# smd_test_rig_with_pico.net
KiCad netlist of a schematic drawn in EAGLE
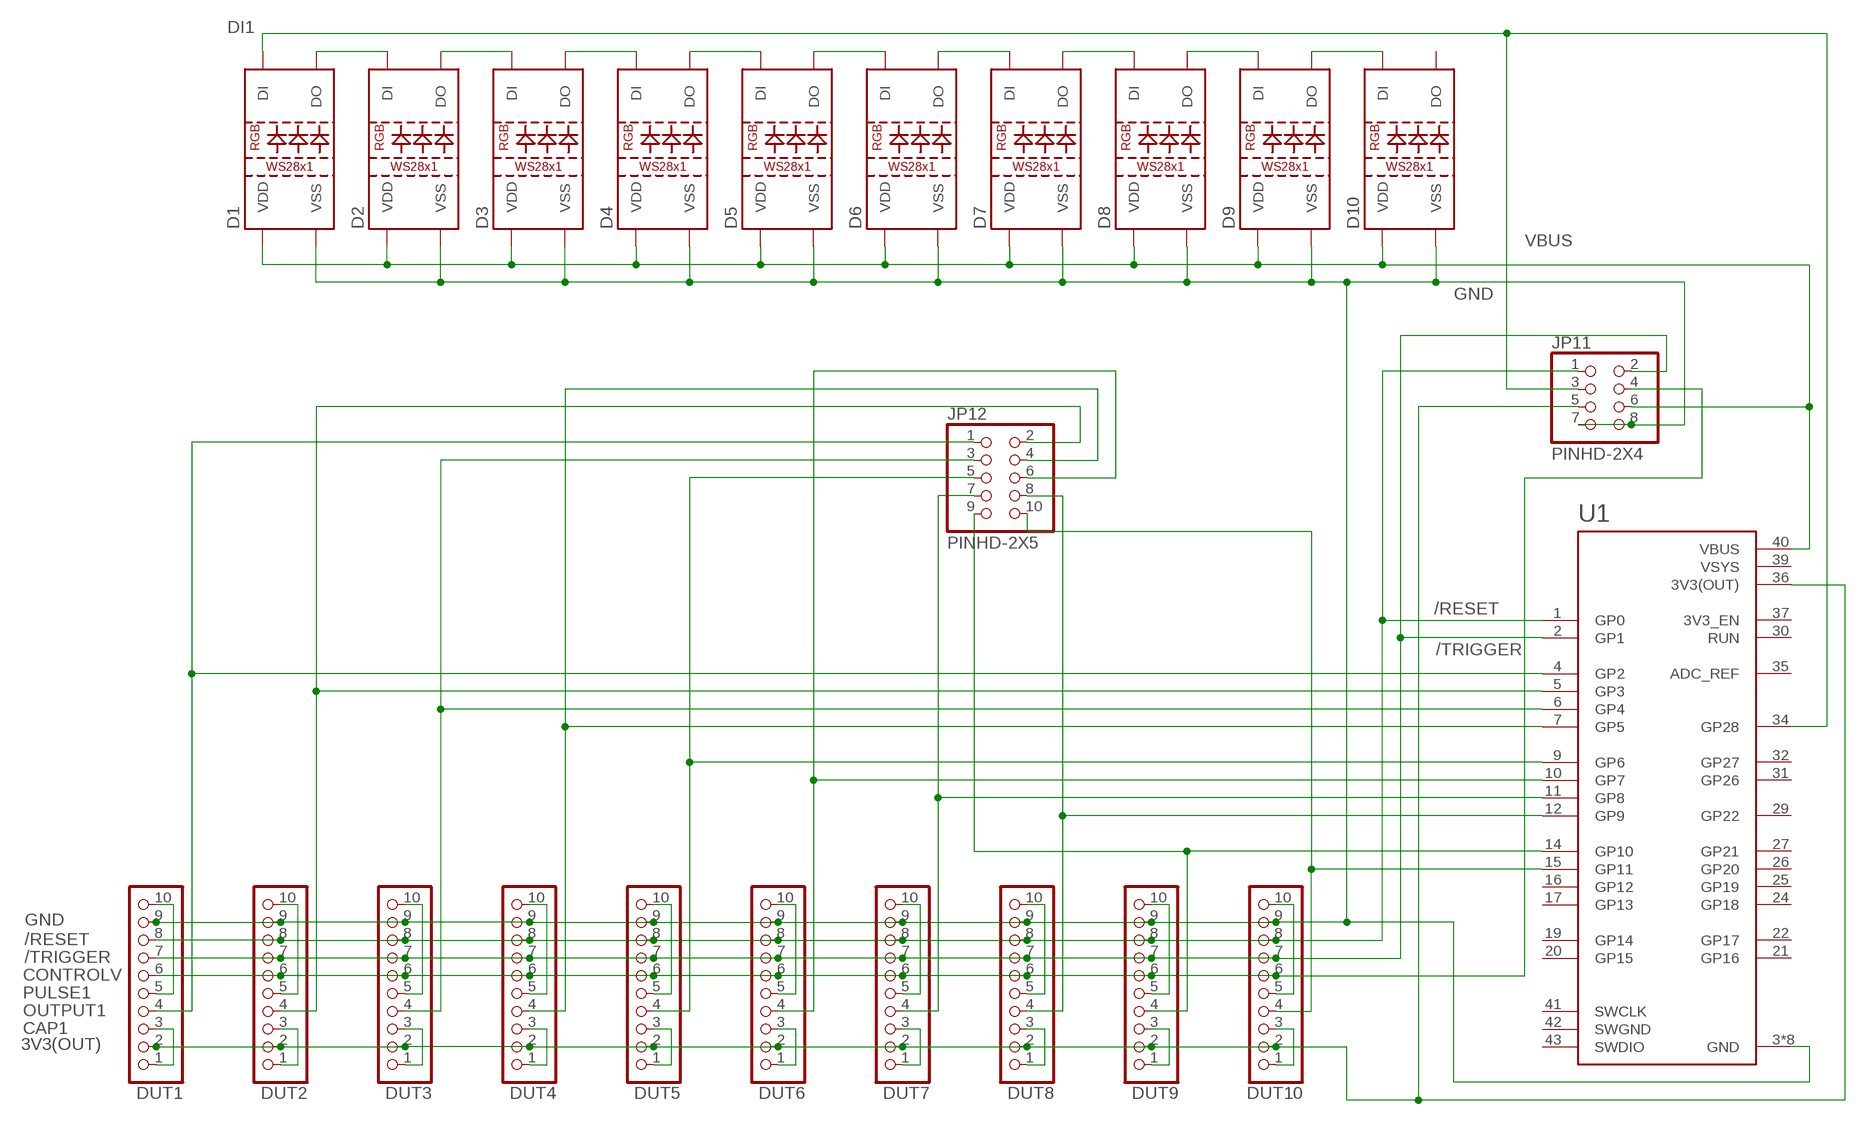
[diagram p0: schematic, sheet 1]

(export (version "E")
  (design (tool "Eeschema 10.0.6"))
  (components
    (comp (ref "D1")
      (value "WS2812B")
      (footprint "eagle-import:WS2812B")
      (libsource (lib "eagle-import") (part "WS2812B"))
    )
    (comp (ref "D2")
      (value "WS2812B")
      (footprint "eagle-import:WS2812B")
      (libsource (lib "eagle-import") (part "WS2812B"))
    )
    (comp (ref "D3")
      (value "WS2812B")
      (footprint "eagle-import:WS2812B")
      (libsource (lib "eagle-import") (part "WS2812B"))
    )
    (comp (ref "D4")
      (value "WS2812B")
      (footprint "eagle-import:WS2812B")
      (libsource (lib "eagle-import") (part "WS2812B"))
    )
    (comp (ref "D5")
      (value "WS2812B")
      (footprint "eagle-import:WS2812B")
      (libsource (lib "eagle-import") (part "WS2812B"))
    )
    (comp (ref "D6")
      (value "WS2812B")
      (footprint "eagle-import:WS2812B")
      (libsource (lib "eagle-import") (part "WS2812B"))
    )
    (comp (ref "D7")
      (value "WS2812B")
      (footprint "eagle-import:WS2812B")
      (libsource (lib "eagle-import") (part "WS2812B"))
    )
    (comp (ref "D8")
      (value "WS2812B")
      (footprint "eagle-import:WS2812B")
      (libsource (lib "eagle-import") (part "WS2812B"))
    )
    (comp (ref "D9")
      (value "WS2812B")
      (footprint "eagle-import:WS2812B")
      (libsource (lib "eagle-import") (part "WS2812B"))
    )
    (comp (ref "D10")
      (value "WS2812B")
      (footprint "eagle-import:WS2812B")
      (libsource (lib "eagle-import") (part "WS2812B"))
    )
    (comp (ref "DUT1")
      (value "PINHD-1X10")
      (footprint "eagle-import:1X10")
      (libsource (lib "eagle-import") (part "PINHD-1X10"))
    )
    (comp (ref "DUT2")
      (value "PINHD-1X10")
      (footprint "eagle-import:1X10")
      (libsource (lib "eagle-import") (part "PINHD-1X10"))
    )
    (comp (ref "DUT3")
      (value "PINHD-1X10")
      (footprint "eagle-import:1X10")
      (libsource (lib "eagle-import") (part "PINHD-1X10"))
    )
    (comp (ref "DUT4")
      (value "PINHD-1X10")
      (footprint "eagle-import:1X10")
      (libsource (lib "eagle-import") (part "PINHD-1X10"))
    )
    (comp (ref "DUT5")
      (value "PINHD-1X10")
      (footprint "eagle-import:1X10")
      (libsource (lib "eagle-import") (part "PINHD-1X10"))
    )
    (comp (ref "DUT6")
      (value "PINHD-1X10")
      (footprint "eagle-import:1X10")
      (libsource (lib "eagle-import") (part "PINHD-1X10"))
    )
    (comp (ref "DUT7")
      (value "PINHD-1X10")
      (footprint "eagle-import:1X10")
      (libsource (lib "eagle-import") (part "PINHD-1X10"))
    )
    (comp (ref "DUT8")
      (value "PINHD-1X10")
      (footprint "eagle-import:1X10")
      (libsource (lib "eagle-import") (part "PINHD-1X10"))
    )
    (comp (ref "DUT9")
      (value "PINHD-1X10")
      (footprint "eagle-import:1X10")
      (libsource (lib "eagle-import") (part "PINHD-1X10"))
    )
    (comp (ref "DUT10")
      (value "PINHD-1X10")
      (footprint "eagle-import:1X10")
      (libsource (lib "eagle-import") (part "PINHD-1X10"))
    )
    (comp (ref "JP11")
      (value "PINHD-2X4")
      (footprint "eagle-import:2X04")
      (libsource (lib "eagle-import") (part "PINHD-2X4"))
    )
    (comp (ref "JP12")
      (value "PINHD-2X5")
      (footprint "eagle-import:2X05")
      (libsource (lib "eagle-import") (part "PINHD-2X5"))
    )
    (comp (ref "U1")
      (value "RASPBERRY_PICO")
      (footprint "eagle-import:PICO-PKG-TH")
      (libsource (lib "eagle-import") (part "RASPBERRY_PICOTH"))
    )
  )
  (nets
    (net (code "1") (name "/3V3(OUT)") (class "Default")
      (node (ref "DUT1") (pin "2") (pinfunction "2_2") (pintype "passive"))
      (node (ref "DUT10") (pin "2") (pinfunction "2_2") (pintype "passive"))
      (node (ref "DUT2") (pin "2") (pinfunction "2_2") (pintype "passive"))
      (node (ref "DUT3") (pin "2") (pinfunction "2_2") (pintype "passive"))
      (node (ref "DUT4") (pin "2") (pinfunction "2_2") (pintype "passive"))
      (node (ref "DUT5") (pin "2") (pinfunction "2_2") (pintype "passive"))
      (node (ref "DUT6") (pin "2") (pinfunction "2_2") (pintype "passive"))
      (node (ref "DUT7") (pin "2") (pinfunction "2_2") (pintype "passive"))
      (node (ref "DUT8") (pin "2") (pinfunction "2_2") (pintype "passive"))
      (node (ref "DUT9") (pin "2") (pinfunction "2_2") (pintype "passive"))
      (node (ref "JP11") (pin "5") (pinfunction "5_5") (pintype "passive"))
      (node (ref "U1") (pin "36") (pinfunction "3V3(OUT)_36") (pintype "power_in"))
    )
    (net (code "2") (name "/CAP1") (class "Default")
      (node (ref "DUT1") (pin "1") (pinfunction "1_1") (pintype "passive"))
      (node (ref "DUT1") (pin "3") (pinfunction "3_3") (pintype "passive"))
    )
    (net (code "3") (name "/CONTROLV") (class "Default")
      (node (ref "DUT1") (pin "6") (pinfunction "6_6") (pintype "passive"))
      (node (ref "DUT10") (pin "6") (pinfunction "6_6") (pintype "passive"))
      (node (ref "DUT2") (pin "6") (pinfunction "6_6") (pintype "passive"))
      (node (ref "DUT3") (pin "6") (pinfunction "6_6") (pintype "passive"))
      (node (ref "DUT4") (pin "6") (pinfunction "6_6") (pintype "passive"))
      (node (ref "DUT5") (pin "6") (pinfunction "6_6") (pintype "passive"))
      (node (ref "DUT6") (pin "6") (pinfunction "6_6") (pintype "passive"))
      (node (ref "DUT7") (pin "6") (pinfunction "6_6") (pintype "passive"))
      (node (ref "DUT8") (pin "6") (pinfunction "6_6") (pintype "passive"))
      (node (ref "DUT9") (pin "6") (pinfunction "6_6") (pintype "passive"))
      (node (ref "JP11") (pin "4") (pinfunction "4_4") (pintype "passive"))
    )
    (net (code "4") (name "/DI1") (class "Default")
      (node (ref "D1") (pin "4") (pinfunction "DI_4") (pintype "bidirectional"))
      (node (ref "JP11") (pin "3") (pinfunction "3_3") (pintype "passive"))
      (node (ref "U1") (pin "34") (pinfunction "GP28_34") (pintype "bidirectional"))
    )
    (net (code "5") (name "/GND") (class "Default")
      (node (ref "D1") (pin "3") (pinfunction "VSS_3") (pintype "bidirectional"))
      (node (ref "D10") (pin "3") (pinfunction "VSS_3") (pintype "bidirectional"))
      (node (ref "D2") (pin "3") (pinfunction "VSS_3") (pintype "bidirectional"))
      (node (ref "D3") (pin "3") (pinfunction "VSS_3") (pintype "bidirectional"))
      (node (ref "D4") (pin "3") (pinfunction "VSS_3") (pintype "bidirectional"))
      (node (ref "D5") (pin "3") (pinfunction "VSS_3") (pintype "bidirectional"))
      (node (ref "D6") (pin "3") (pinfunction "VSS_3") (pintype "bidirectional"))
      (node (ref "D7") (pin "3") (pinfunction "VSS_3") (pintype "bidirectional"))
      (node (ref "D8") (pin "3") (pinfunction "VSS_3") (pintype "bidirectional"))
      (node (ref "D9") (pin "3") (pinfunction "VSS_3") (pintype "bidirectional"))
      (node (ref "DUT1") (pin "9") (pinfunction "9_9") (pintype "passive"))
      (node (ref "DUT10") (pin "9") (pinfunction "9_9") (pintype "passive"))
      (node (ref "DUT2") (pin "9") (pinfunction "9_9") (pintype "passive"))
      (node (ref "DUT3") (pin "9") (pinfunction "9_9") (pintype "passive"))
      (node (ref "DUT4") (pin "9") (pinfunction "9_9") (pintype "passive"))
      (node (ref "DUT5") (pin "9") (pinfunction "9_9") (pintype "passive"))
      (node (ref "DUT6") (pin "9") (pinfunction "9_9") (pintype "passive"))
      (node (ref "DUT7") (pin "9") (pinfunction "9_9") (pintype "passive"))
      (node (ref "DUT8") (pin "9") (pinfunction "9_9") (pintype "passive"))
      (node (ref "DUT9") (pin "9") (pinfunction "9_9") (pintype "passive"))
      (node (ref "JP11") (pin "7") (pinfunction "7_7") (pintype "passive"))
      (node (ref "JP11") (pin "8") (pinfunction "8_8") (pintype "passive"))
      (node (ref "U1") (pin "13") (pinfunction "GND_13") (pintype "power_in"))
      (node (ref "U1") (pin "18") (pinfunction "GND_18") (pintype "power_in"))
      (node (ref "U1") (pin "23") (pinfunction "GND_23") (pintype "power_in"))
      (node (ref "U1") (pin "28") (pinfunction "GND_28") (pintype "power_in"))
      (node (ref "U1") (pin "3") (pinfunction "GND_3") (pintype "power_in"))
      (node (ref "U1") (pin "33") (pinfunction "GND_33") (pintype "power_in"))
      (node (ref "U1") (pin "38") (pinfunction "GND_38") (pintype "power_in"))
      (node (ref "U1") (pin "8") (pinfunction "GND_8") (pintype "power_in"))
    )
    (net (code "6") (name "/OUTPUT1") (class "Default")
      (node (ref "DUT1") (pin "4") (pinfunction "4_4") (pintype "passive"))
      (node (ref "JP12") (pin "1") (pinfunction "1_1") (pintype "passive"))
      (node (ref "U1") (pin "4") (pinfunction "GP2_4") (pintype "bidirectional"))
    )
    (net (code "7") (name "/PULSE1") (class "Default")
      (node (ref "DUT1") (pin "10") (pinfunction "10_10") (pintype "passive"))
      (node (ref "DUT1") (pin "5") (pinfunction "5_5") (pintype "passive"))
    )
    (net (code "8") (name "/SWGND") (class "Default")
      (node (ref "U1") (pin "42") (pinfunction "SWGND_42") (pintype "power_in"))
    )
    (net (code "9") (name "/VBUS") (class "Default")
      (node (ref "D1") (pin "1") (pinfunction "VDD_1") (pintype "bidirectional"))
      (node (ref "D10") (pin "1") (pinfunction "VDD_1") (pintype "bidirectional"))
      (node (ref "D2") (pin "1") (pinfunction "VDD_1") (pintype "bidirectional"))
      (node (ref "D3") (pin "1") (pinfunction "VDD_1") (pintype "bidirectional"))
      (node (ref "D4") (pin "1") (pinfunction "VDD_1") (pintype "bidirectional"))
      (node (ref "D5") (pin "1") (pinfunction "VDD_1") (pintype "bidirectional"))
      (node (ref "D6") (pin "1") (pinfunction "VDD_1") (pintype "bidirectional"))
      (node (ref "D7") (pin "1") (pinfunction "VDD_1") (pintype "bidirectional"))
      (node (ref "D8") (pin "1") (pinfunction "VDD_1") (pintype "bidirectional"))
      (node (ref "D9") (pin "1") (pinfunction "VDD_1") (pintype "bidirectional"))
      (node (ref "JP11") (pin "6") (pinfunction "6_6") (pintype "passive"))
      (node (ref "U1") (pin "40") (pinfunction "VBUS_40") (pintype "power_in"))
    )
    (net (code "10") (name "/VSYS") (class "Default")
      (node (ref "U1") (pin "39") (pinfunction "VSYS_39") (pintype "power_in"))
    )
    (net (code "11") (name "/{slash}RESET") (class "Default")
      (node (ref "DUT1") (pin "8") (pinfunction "8_8") (pintype "passive"))
      (node (ref "DUT10") (pin "8") (pinfunction "8_8") (pintype "passive"))
      (node (ref "DUT2") (pin "8") (pinfunction "8_8") (pintype "passive"))
      (node (ref "DUT3") (pin "8") (pinfunction "8_8") (pintype "passive"))
      (node (ref "DUT4") (pin "8") (pinfunction "8_8") (pintype "passive"))
      (node (ref "DUT5") (pin "8") (pinfunction "8_8") (pintype "passive"))
      (node (ref "DUT6") (pin "8") (pinfunction "8_8") (pintype "passive"))
      (node (ref "DUT7") (pin "8") (pinfunction "8_8") (pintype "passive"))
      (node (ref "DUT8") (pin "8") (pinfunction "8_8") (pintype "passive"))
      (node (ref "DUT9") (pin "8") (pinfunction "8_8") (pintype "passive"))
      (node (ref "JP11") (pin "1") (pinfunction "1_1") (pintype "passive"))
      (node (ref "U1") (pin "1") (pinfunction "GP0_1") (pintype "bidirectional"))
    )
    (net (code "12") (name "/{slash}TRIGGER") (class "Default")
      (node (ref "DUT1") (pin "7") (pinfunction "7_7") (pintype "passive"))
      (node (ref "DUT10") (pin "7") (pinfunction "7_7") (pintype "passive"))
      (node (ref "DUT2") (pin "7") (pinfunction "7_7") (pintype "passive"))
      (node (ref "DUT3") (pin "7") (pinfunction "7_7") (pintype "passive"))
      (node (ref "DUT4") (pin "7") (pinfunction "7_7") (pintype "passive"))
      (node (ref "DUT5") (pin "7") (pinfunction "7_7") (pintype "passive"))
      (node (ref "DUT6") (pin "7") (pinfunction "7_7") (pintype "passive"))
      (node (ref "DUT7") (pin "7") (pinfunction "7_7") (pintype "passive"))
      (node (ref "DUT8") (pin "7") (pinfunction "7_7") (pintype "passive"))
      (node (ref "DUT9") (pin "7") (pinfunction "7_7") (pintype "passive"))
      (node (ref "JP11") (pin "2") (pinfunction "2_2") (pintype "passive"))
      (node (ref "U1") (pin "2") (pinfunction "GP1_2") (pintype "bidirectional"))
    )
    (net (code "13") (name "Net-(D1-DO)") (class "Default")
      (node (ref "D1") (pin "2") (pinfunction "DO_2") (pintype "bidirectional"))
      (node (ref "D2") (pin "4") (pinfunction "DI_4") (pintype "bidirectional"))
    )
    (net (code "14") (name "Net-(D2-DO)") (class "Default")
      (node (ref "D2") (pin "2") (pinfunction "DO_2") (pintype "bidirectional"))
      (node (ref "D3") (pin "4") (pinfunction "DI_4") (pintype "bidirectional"))
    )
    (net (code "15") (name "Net-(D3-DO)") (class "Default")
      (node (ref "D3") (pin "2") (pinfunction "DO_2") (pintype "bidirectional"))
      (node (ref "D4") (pin "4") (pinfunction "DI_4") (pintype "bidirectional"))
    )
    (net (code "16") (name "Net-(D4-DO)") (class "Default")
      (node (ref "D4") (pin "2") (pinfunction "DO_2") (pintype "bidirectional"))
      (node (ref "D5") (pin "4") (pinfunction "DI_4") (pintype "bidirectional"))
    )
    (net (code "17") (name "Net-(D5-DO)") (class "Default")
      (node (ref "D5") (pin "2") (pinfunction "DO_2") (pintype "bidirectional"))
      (node (ref "D6") (pin "4") (pinfunction "DI_4") (pintype "bidirectional"))
    )
    (net (code "18") (name "Net-(D6-DO)") (class "Default")
      (node (ref "D6") (pin "2") (pinfunction "DO_2") (pintype "bidirectional"))
      (node (ref "D7") (pin "4") (pinfunction "DI_4") (pintype "bidirectional"))
    )
    (net (code "19") (name "Net-(D7-DO)") (class "Default")
      (node (ref "D7") (pin "2") (pinfunction "DO_2") (pintype "bidirectional"))
      (node (ref "D8") (pin "4") (pinfunction "DI_4") (pintype "bidirectional"))
    )
    (net (code "20") (name "Net-(D8-DO)") (class "Default")
      (node (ref "D8") (pin "2") (pinfunction "DO_2") (pintype "bidirectional"))
      (node (ref "D9") (pin "4") (pinfunction "DI_4") (pintype "bidirectional"))
    )
    (net (code "21") (name "Net-(D10-DI)") (class "Default")
      (node (ref "D10") (pin "4") (pinfunction "DI_4") (pintype "bidirectional"))
      (node (ref "D9") (pin "2") (pinfunction "DO_2") (pintype "bidirectional"))
    )
    (net (code "22") (name "Net-(DUT2-Pad1)") (class "Default")
      (node (ref "DUT2") (pin "1") (pinfunction "1_1") (pintype "passive"))
      (node (ref "DUT2") (pin "3") (pinfunction "3_3") (pintype "passive"))
    )
    (net (code "23") (name "Net-(DUT2-Pad10)") (class "Default")
      (node (ref "DUT2") (pin "10") (pinfunction "10_10") (pintype "passive"))
      (node (ref "DUT2") (pin "5") (pinfunction "5_5") (pintype "passive"))
    )
    (net (code "24") (name "Net-(DUT3-Pad1)") (class "Default")
      (node (ref "DUT3") (pin "1") (pinfunction "1_1") (pintype "passive"))
      (node (ref "DUT3") (pin "3") (pinfunction "3_3") (pintype "passive"))
    )
    (net (code "25") (name "Net-(DUT3-Pad10)") (class "Default")
      (node (ref "DUT3") (pin "10") (pinfunction "10_10") (pintype "passive"))
      (node (ref "DUT3") (pin "5") (pinfunction "5_5") (pintype "passive"))
    )
    (net (code "26") (name "Net-(DUT4-Pad1)") (class "Default")
      (node (ref "DUT4") (pin "1") (pinfunction "1_1") (pintype "passive"))
      (node (ref "DUT4") (pin "3") (pinfunction "3_3") (pintype "passive"))
    )
    (net (code "27") (name "Net-(DUT4-Pad10)") (class "Default")
      (node (ref "DUT4") (pin "10") (pinfunction "10_10") (pintype "passive"))
      (node (ref "DUT4") (pin "5") (pinfunction "5_5") (pintype "passive"))
    )
    (net (code "28") (name "Net-(DUT5-Pad1)") (class "Default")
      (node (ref "DUT5") (pin "1") (pinfunction "1_1") (pintype "passive"))
      (node (ref "DUT5") (pin "3") (pinfunction "3_3") (pintype "passive"))
    )
    (net (code "29") (name "Net-(DUT5-Pad10)") (class "Default")
      (node (ref "DUT5") (pin "10") (pinfunction "10_10") (pintype "passive"))
      (node (ref "DUT5") (pin "5") (pinfunction "5_5") (pintype "passive"))
    )
    (net (code "30") (name "Net-(DUT6-Pad1)") (class "Default")
      (node (ref "DUT6") (pin "1") (pinfunction "1_1") (pintype "passive"))
      (node (ref "DUT6") (pin "3") (pinfunction "3_3") (pintype "passive"))
    )
    (net (code "31") (name "Net-(DUT6-Pad10)") (class "Default")
      (node (ref "DUT6") (pin "10") (pinfunction "10_10") (pintype "passive"))
      (node (ref "DUT6") (pin "5") (pinfunction "5_5") (pintype "passive"))
    )
    (net (code "32") (name "Net-(DUT7-Pad1)") (class "Default")
      (node (ref "DUT7") (pin "1") (pinfunction "1_1") (pintype "passive"))
      (node (ref "DUT7") (pin "3") (pinfunction "3_3") (pintype "passive"))
    )
    (net (code "33") (name "Net-(DUT7-Pad10)") (class "Default")
      (node (ref "DUT7") (pin "10") (pinfunction "10_10") (pintype "passive"))
      (node (ref "DUT7") (pin "5") (pinfunction "5_5") (pintype "passive"))
    )
    (net (code "34") (name "Net-(DUT8-Pad1)") (class "Default")
      (node (ref "DUT8") (pin "1") (pinfunction "1_1") (pintype "passive"))
      (node (ref "DUT8") (pin "3") (pinfunction "3_3") (pintype "passive"))
    )
    (net (code "35") (name "Net-(DUT8-Pad10)") (class "Default")
      (node (ref "DUT8") (pin "10") (pinfunction "10_10") (pintype "passive"))
      (node (ref "DUT8") (pin "5") (pinfunction "5_5") (pintype "passive"))
    )
    (net (code "36") (name "Net-(DUT9-Pad1)") (class "Default")
      (node (ref "DUT9") (pin "1") (pinfunction "1_1") (pintype "passive"))
      (node (ref "DUT9") (pin "3") (pinfunction "3_3") (pintype "passive"))
    )
    (net (code "37") (name "Net-(DUT9-Pad10)") (class "Default")
      (node (ref "DUT9") (pin "10") (pinfunction "10_10") (pintype "passive"))
      (node (ref "DUT9") (pin "5") (pinfunction "5_5") (pintype "passive"))
    )
    (net (code "38") (name "Net-(DUT10-Pad1)") (class "Default")
      (node (ref "DUT10") (pin "1") (pinfunction "1_1") (pintype "passive"))
      (node (ref "DUT10") (pin "3") (pinfunction "3_3") (pintype "passive"))
    )
    (net (code "39") (name "Net-(DUT10-Pad10)") (class "Default")
      (node (ref "DUT10") (pin "10") (pinfunction "10_10") (pintype "passive"))
      (node (ref "DUT10") (pin "5") (pinfunction "5_5") (pintype "passive"))
    )
    (net (code "40") (name "Net-(U1-GP3)") (class "Default")
      (node (ref "DUT2") (pin "4") (pinfunction "4_4") (pintype "passive"))
      (node (ref "JP12") (pin "2") (pinfunction "2_2") (pintype "passive"))
      (node (ref "U1") (pin "5") (pinfunction "GP3_5") (pintype "bidirectional"))
    )
    (net (code "41") (name "Net-(U1-GP4)") (class "Default")
      (node (ref "DUT3") (pin "4") (pinfunction "4_4") (pintype "passive"))
      (node (ref "JP12") (pin "3") (pinfunction "3_3") (pintype "passive"))
      (node (ref "U1") (pin "6") (pinfunction "GP4_6") (pintype "bidirectional"))
    )
    (net (code "42") (name "Net-(U1-GP5)") (class "Default")
      (node (ref "DUT4") (pin "4") (pinfunction "4_4") (pintype "passive"))
      (node (ref "JP12") (pin "4") (pinfunction "4_4") (pintype "passive"))
      (node (ref "U1") (pin "7") (pinfunction "GP5_7") (pintype "bidirectional"))
    )
    (net (code "43") (name "Net-(U1-GP6)") (class "Default")
      (node (ref "DUT5") (pin "4") (pinfunction "4_4") (pintype "passive"))
      (node (ref "JP12") (pin "5") (pinfunction "5_5") (pintype "passive"))
      (node (ref "U1") (pin "9") (pinfunction "GP6_9") (pintype "bidirectional"))
    )
    (net (code "44") (name "Net-(U1-GP7)") (class "Default")
      (node (ref "DUT6") (pin "4") (pinfunction "4_4") (pintype "passive"))
      (node (ref "JP12") (pin "6") (pinfunction "6_6") (pintype "passive"))
      (node (ref "U1") (pin "10") (pinfunction "GP7_10") (pintype "bidirectional"))
    )
    (net (code "45") (name "Net-(U1-GP8)") (class "Default")
      (node (ref "DUT7") (pin "4") (pinfunction "4_4") (pintype "passive"))
      (node (ref "JP12") (pin "7") (pinfunction "7_7") (pintype "passive"))
      (node (ref "U1") (pin "11") (pinfunction "GP8_11") (pintype "bidirectional"))
    )
    (net (code "46") (name "Net-(U1-GP9)") (class "Default")
      (node (ref "DUT8") (pin "4") (pinfunction "4_4") (pintype "passive"))
      (node (ref "JP12") (pin "8") (pinfunction "8_8") (pintype "passive"))
      (node (ref "U1") (pin "12") (pinfunction "GP9_12") (pintype "bidirectional"))
    )
    (net (code "47") (name "Net-(U1-GP10)") (class "Default")
      (node (ref "DUT9") (pin "4") (pinfunction "4_4") (pintype "passive"))
      (node (ref "JP12") (pin "9") (pinfunction "9_9") (pintype "passive"))
      (node (ref "U1") (pin "14") (pinfunction "GP10_14") (pintype "bidirectional"))
    )
    (net (code "48") (name "Net-(U1-GP11)") (class "Default")
      (node (ref "DUT10") (pin "4") (pinfunction "4_4") (pintype "passive"))
      (node (ref "JP12") (pin "10") (pinfunction "10_10") (pintype "passive"))
      (node (ref "U1") (pin "15") (pinfunction "GP11_15") (pintype "bidirectional"))
    )
    (net (code "49") (name "unconnected-(D10-DO-Pad2)") (class "Default")
      (node (ref "D10") (pin "2") (pinfunction "DO_2") (pintype "bidirectional"))
    )
    (net (code "50") (name "unconnected-(U1-3V3_EN-Pad37)") (class "Default")
      (node (ref "U1") (pin "37") (pinfunction "3V3_EN_37") (pintype "input"))
    )
    (net (code "51") (name "unconnected-(U1-ADC_REF-Pad35)") (class "Default")
      (node (ref "U1") (pin "35") (pinfunction "ADC_REF_35") (pintype "input"))
    )
    (net (code "52") (name "unconnected-(U1-GP12-Pad16)") (class "Default")
      (node (ref "U1") (pin "16") (pinfunction "GP12_16") (pintype "bidirectional"))
    )
    (net (code "53") (name "unconnected-(U1-GP13-Pad17)") (class "Default")
      (node (ref "U1") (pin "17") (pinfunction "GP13_17") (pintype "bidirectional"))
    )
    (net (code "54") (name "unconnected-(U1-GP14-Pad19)") (class "Default")
      (node (ref "U1") (pin "19") (pinfunction "GP14_19") (pintype "bidirectional"))
    )
    (net (code "55") (name "unconnected-(U1-GP15-Pad20)") (class "Default")
      (node (ref "U1") (pin "20") (pinfunction "GP15_20") (pintype "bidirectional"))
    )
    (net (code "56") (name "unconnected-(U1-GP16-Pad21)") (class "Default")
      (node (ref "U1") (pin "21") (pinfunction "GP16_21") (pintype "bidirectional"))
    )
    (net (code "57") (name "unconnected-(U1-GP17-Pad22)") (class "Default")
      (node (ref "U1") (pin "22") (pinfunction "GP17_22") (pintype "bidirectional"))
    )
    (net (code "58") (name "unconnected-(U1-GP18-Pad24)") (class "Default")
      (node (ref "U1") (pin "24") (pinfunction "GP18_24") (pintype "bidirectional"))
    )
    (net (code "59") (name "unconnected-(U1-GP19-Pad25)") (class "Default")
      (node (ref "U1") (pin "25") (pinfunction "GP19_25") (pintype "bidirectional"))
    )
    (net (code "60") (name "unconnected-(U1-GP20-Pad26)") (class "Default")
      (node (ref "U1") (pin "26") (pinfunction "GP20_26") (pintype "bidirectional"))
    )
    (net (code "61") (name "unconnected-(U1-GP21-Pad27)") (class "Default")
      (node (ref "U1") (pin "27") (pinfunction "GP21_27") (pintype "bidirectional"))
    )
    (net (code "62") (name "unconnected-(U1-GP22-Pad29)") (class "Default")
      (node (ref "U1") (pin "29") (pinfunction "GP22_29") (pintype "bidirectional"))
    )
    (net (code "63") (name "unconnected-(U1-GP26-Pad31)") (class "Default")
      (node (ref "U1") (pin "31") (pinfunction "GP26_31") (pintype "bidirectional"))
    )
    (net (code "64") (name "unconnected-(U1-GP27-Pad32)") (class "Default")
      (node (ref "U1") (pin "32") (pinfunction "GP27_32") (pintype "bidirectional"))
    )
    (net (code "65") (name "unconnected-(U1-RUN-Pad30)") (class "Default")
      (node (ref "U1") (pin "30") (pinfunction "RUN_30") (pintype "input"))
    )
    (net (code "66") (name "unconnected-(U1-SWCLK-Pad41)") (class "Default")
      (node (ref "U1") (pin "41") (pinfunction "SWCLK_41") (pintype "input"))
    )
    (net (code "67") (name "unconnected-(U1-SWDIO-Pad43)") (class "Default")
      (node (ref "U1") (pin "43") (pinfunction "SWDIO_43") (pintype "bidirectional"))
    )
  )
)
